# PowerSupply.net
KiCad netlist of a schematic drawn in Altium Designer
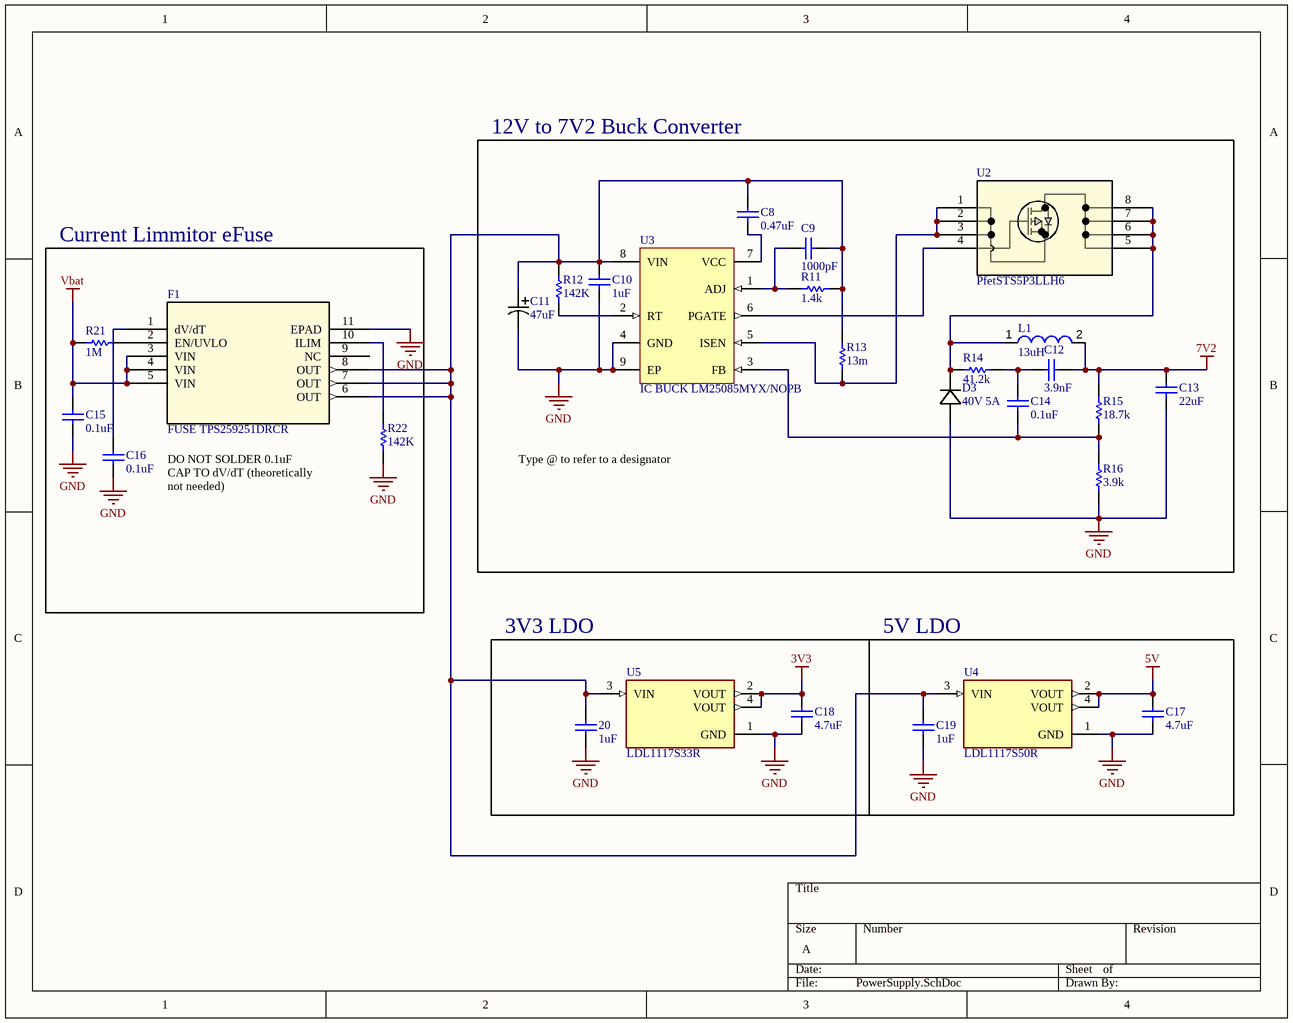
[diagram p0: PowerSupply.SchDoc]

(export (version "E")
  (design (tool "Eeschema 10.0.6"))
  (components
    (comp (ref "20")
      (value "1uF")
      (footprint "RES 0805")
      (fields
        (field (name "MANUFACTURER") "Samsung")
        (field (name "MANUFACTURER PART NUMBER") "CL21B105KBFNNNE")
      )
      (libsource (lib "Schlib1") (part "CAP CER 1uF 10% 50V 0805"))
    )
    (comp (ref "C8")
      (value "0.47uF")
      (footprint "RES 0805")
      (fields
        (field (name "MANUFACTURER") "Murata")
        (field (name "MANUFACTURER PART NUMBER") "GRM21BR71H474KA88L")
      )
      (libsource (lib "Schlib1") (part "CAP CER 0.47uF 10% 50V 0805"))
    )
    (comp (ref "C9")
      (value "1000pF")
      (footprint "RES 0805")
      (fields
        (field (name "MANUFACTURER") "KEMET")
        (field (name "MANUFACTURER PART NUMBER") "C0805C102K5RACTU")
      )
      (libsource (lib "Schlib1") (part "CAP CER 1000pF 10% 50V 0805"))
    )
    (comp (ref "C10")
      (value "1uF")
      (footprint "RES 0805")
      (fields
        (field (name "MANUFACTURER") "Samsung")
        (field (name "MANUFACTURER PART NUMBER") "CL21B105KBFNNNE")
      )
      (libsource (lib "Schlib1") (part "CAP CER 1uF 10% 50V 0805"))
    )
    (comp (ref "C11")
      (value "47uF")
      (footprint "CAP ELC 47uF")
      (fields
        (field (name "MANUFACTURER") "Nichicon")
        (field (name "MANUFACTURER PART NUMBER") "UWT1H470MCL1GS")
      )
      (libsource (lib "Schlib1") (part "CAP ELCALUM 47uF 20% 50V"))
    )
    (comp (ref "C12")
      (value "3.9nF")
      (footprint "RES 0805")
      (fields
        (field (name "MANUFACTURER") "Yageo")
        (field (name "MANUFACTURER PART NUMBER") "CC0805KRX7R9BB392")
      )
      (libsource (lib "Schlib1") (part "CAP CER 3.9nF 10% 50V 0805"))
    )
    (comp (ref "C13")
      (value "22uF")
      (footprint "RES 0805")
      (fields
        (field (name "MANUFACTURER") "Samsung")
        (field (name "MANUFACTURER PART NUMBER") "CL21A226MAYNNNE")
      )
      (libsource (lib "Schlib1") (part "CAP CER 22uF 20% 25V 0805"))
    )
    (comp (ref "C14")
      (value "0.1uF")
      (footprint "RES 0805")
      (fields
        (field (name "MANUFACTURER") "Yageo")
        (field (name "MANUFACTURER PART NUMBER") "CC0805KRX7R9BB104")
      )
      (libsource (lib "Schlib1") (part "CAP CER 0.1uF 10% 50V 0805"))
    )
    (comp (ref "C15")
      (value "0.1uF")
      (footprint "RES 0805")
      (fields
        (field (name "MANUFACTURER") "Yageo")
        (field (name "MANUFACTURER PART NUMBER") "CC0805KRX7R9BB104")
      )
      (libsource (lib "Schlib1") (part "CAP CER 0.1uF 10% 50V 0805"))
    )
    (comp (ref "C16")
      (value "0.1uF")
      (footprint "RES 0805")
      (fields
        (field (name "MANUFACTURER") "Yageo")
        (field (name "MANUFACTURER PART NUMBER") "CC0805KRX7R9BB104")
      )
      (libsource (lib "Schlib1") (part "CAP CER 0.1uF 10% 50V 0805"))
    )
    (comp (ref "C17")
      (value "4.7uF")
      (footprint "RES 0805")
      (fields
        (field (name "MANUFACTURER") "Samsung")
        (field (name "MANUFACTURER PART NUMBER") "CL21A475KAQNNNE")
      )
      (libsource (lib "Schlib1") (part "CAP CER 4.7uF 10% 25V 0805"))
    )
    (comp (ref "C18")
      (value "4.7uF")
      (footprint "RES 0805")
      (fields
        (field (name "MANUFACTURER") "Samsung")
        (field (name "MANUFACTURER PART NUMBER") "CL21A475KAQNNNE")
      )
      (libsource (lib "Schlib1") (part "CAP CER 4.7uF 10% 25V 0805"))
    )
    (comp (ref "C19")
      (value "1uF")
      (footprint "RES 0805")
      (fields
        (field (name "MANUFACTURER") "Samsung")
        (field (name "MANUFACTURER PART NUMBER") "CL21B105KBFNNNE")
      )
      (libsource (lib "Schlib1") (part "CAP CER 1uF 10% 50V 0805"))
    )
    (comp (ref "D3")
      (value "40V 5A")
      (footprint "DIODE SCHOTTKY 40V 5A")
      (description "Rectifier Diode, Schottky, 1 Phase, 1 Element, 5A, 40V V(RRM), Silicon, DO-214AC")
      (fields (field (name "MANUFACTURER") "MCC") (field (name "MANUFACTURER PART NUMBER") "SK54A-LTP"))
      (libsource (lib "Schlib1") (part "DIODE SCHOTTKY 40V 5A"))
    )
    (comp (ref "F1")
      (value "FUSE TPS259251DRCR")
      (footprint "DRC10_1P65X2P40_TEX")
      (description "Power Supply Support Circuit, Adjustable, 1 Channel, PDSO10")
      (fields
        (field (name "MANUFACTURER") "Texas Instruments")
        (field (name "MANUFACTURER PART NUMBER") "TPS259251DRCR")
      )
      (libsource (lib "Schlib1") (part "FUSE TPS259251DRCR"))
    )
    (comp (ref "L1")
      (value "13uH")
      (footprint "IND 13UH 9A 24 MOHM SMD")
      (description "General Purpose Inductor, 13uH, 20%, 1 Element, SMD, 5550")
      (fields (field (name "MANUFACTURER") "Pulse") (field (name "MANUFACTURER PART NUMBER") "PA4343.133NLT"))
      (libsource (lib "Schlib1") (part "IND 13uH 9A"))
    )
    (comp (ref "R11")
      (value "1.4k")
      (footprint "RES 0805")
      (fields
        (field (name "MANUFACTURER") "Yageo")
        (field (name "MANUFACTURER PART NUMBER") "RC0805FR-071K4L")
        (field (name "TOLERANCE") "1%")
      )
      (libsource (lib "Schlib1") (part "RES 1.4k 1% 0.125W 0805"))
    )
    (comp (ref "R12")
      (value "142K")
      (footprint "RES 0805")
      (description "Fixed Resistor, Thin Film, 0.125W, 142000ohm, 150V, 0.1% +/-Tol, 25ppm/Cel, Surface Mount, 0805")
      (fields
        (field (name "MANUFACTURER") "Yageo")
        (field (name "MANUFACTURER PART NUMBER") "RT0805BRD07142KL")
      )
      (libsource (lib "Schlib1") (part "RES 142K 0.1% 1/8W 0805"))
    )
    (comp (ref "R13")
      (value "13m")
      (footprint "RES 0805")
      (description "Resistor Thick Film 0.013Ohm 0.5% 0.5W 2-Pin 0805 T/R")
      (fields
        (field (name "MANUFACTURER") "Panasonic")
        (field (name "MANUFACTURER PART NUMBER") "ERJ-6CWDR013V")
      )
      (libsource (lib "Schlib1") (part "RES 13m 0.5% 0.5W 0805"))
    )
    (comp (ref "R14")
      (value "41.2k")
      (footprint "RES 0805")
      (fields
        (field (name "MANUFACTURER") "Vishay")
        (field (name "MANUFACTURER PART NUMBER") "CRCW080541K2FKEA")
        (field (name "TOLERANCE") "1%")
      )
      (libsource (lib "Schlib1") (part "RES 41.2K 1% 0.125W 0805"))
    )
    (comp (ref "R15")
      (value "18.7k")
      (footprint "RES 0805")
      (fields
        (field (name "MANUFACTURER") "Stackpole Electronics")
        (field (name "MANUFACTURER PART NUMBER") "RMCF0805FT18K7")
        (field (name "TOLERANCE") "1%")
      )
      (libsource (lib "Schlib1") (part "RES 18.7k 1% 0.125W 0805"))
    )
    (comp (ref "R16")
      (value "3.9k")
      (footprint "RES 0805")
      (fields
        (field (name "MANUFACTURER") "Stackpole Electronics")
        (field (name "MANUFACTURER PART NUMBER") "RMCF0805FT3K92")
        (field (name "TOLERANCE") "1%")
      )
      (libsource (lib "Schlib1") (part "RES 3.9k 1% 0.125W 0805"))
    )
    (comp (ref "R21")
      (value "1M")
      (footprint "RES 0805")
      (description "Fixed Resistor, Thin Film, 0.125W, 1000000ohm, 150V, 0.1% +/-Tol, 10ppm/Cel, Surface Mount, 0805")
      (fields
        (field (name "MANUFACTURER") "Vishay Dale")
        (field (name "MANUFACTURER PART NUMBER") "TNPW08051M00BYEA")
      )
      (libsource (lib "Schlib1") (part "RES 1M 0.1% 0.26W 0805"))
    )
    (comp (ref "R22")
      (value "142K")
      (footprint "RES 0805")
      (description "Fixed Resistor, Thin Film, 0.125W, 142000ohm, 150V, 0.1% +/-Tol, 25ppm/Cel, Surface Mount, 0805")
      (fields
        (field (name "MANUFACTURER") "Yageo")
        (field (name "MANUFACTURER PART NUMBER") "RT0805BRD07142KL")
      )
      (libsource (lib "Schlib1") (part "RES 142K 0.1% 1/8W 0805"))
    )
    (comp (ref "U2")
      (value "PfetSTS5P3LLH6")
      (footprint "STS5P3LLH6")
      (description "Power Field-Effect Transistor, 5A I(D), 1-Element, P-Channel, Metal-oxide Semiconductor FET")
      (fields
        (field (name "MANUFACTURER") "STMicroelectronics")
        (field (name "MANUFACTURER PART NUMBER") "STS5P3LLH6")
      )
      (libsource (lib "Schlib1") (part "PfetSTS5P3LLH6"))
    )
    (comp (ref "U3")
      (value "IC BUCK LM25085MYX/NOPB")
      (description "Switching Controller, Voltage-mode, 10A, 1000kHz Switching Freq-Max, PDSO8")
      (fields
        (field (name "MANUFACTURER") "TI National Semiconductor")
        (field (name "MANUFACTURER PART NUMBER") "LM25085MYX/NOPB")
      )
      (libsource (lib "Schlib1") (part "IC BUCK LM25085MYX/NOPB"))
    )
    (comp (ref "U4")
      (value "LDL1117S50R")
      (footprint "SOT230P700X180-4N")
      (description "Fixed Positive LDO Regulator, 5V, 0.6V Dropout, PDSO4")
      (fields (field (name "MANUFACTURER") "STMicroelectronics"))
      (libsource (lib "Schlib1") (part "LDL1117S50R"))
    )
    (comp (ref "U5")
      (value "LDL1117S33R")
      (footprint "SOT230P700X180-4N")
      (description "Fixed Positive LDO Regulator, 3.3V, 0.6V Dropout, PDSO4")
      (fields (field (name "MANUFACTURER") "STMicroelectronics"))
      (libsource (lib "Schlib1") (part "LDL1117S33R"))
    )
  )
  (nets
    (net (code "1") (name "3V3") (class "Default")
      (node (ref "C18") (pin "2") (pinfunction "2_2") (pintype "passive"))
      (node (ref "U5") (pin "2") (pinfunction "VOUT_2") (pintype "output"))
      (node (ref "U5") (pin "4") (pinfunction "VOUT_4") (pintype "output"))
    )
    (net (code "2") (name "5V") (class "Default")
      (node (ref "C17") (pin "2") (pinfunction "2_2") (pintype "passive"))
      (node (ref "U4") (pin "2") (pinfunction "VOUT_2") (pintype "output"))
      (node (ref "U4") (pin "4") (pinfunction "VOUT_4") (pintype "output"))
    )
    (net (code "3") (name "7V2") (class "Default")
      (node (ref "C12") (pin "2") (pinfunction "2_2") (pintype "passive"))
      (node (ref "C13") (pin "2") (pinfunction "2_2") (pintype "passive"))
      (node (ref "L1") (pin "2") (pinfunction "2_2") (pintype "passive"))
      (node (ref "R15") (pin "2") (pinfunction "2_2") (pintype "passive"))
    )
    (net (code "4") (name "GND") (class "Default")
      (node (ref "20") (pin "1") (pinfunction "1_1") (pintype "passive"))
      (node (ref "C10") (pin "1") (pinfunction "1_1") (pintype "passive"))
      (node (ref "C11") (pin "2") (pinfunction "2_2") (pintype "passive"))
      (node (ref "C13") (pin "1") (pinfunction "1_1") (pintype "passive"))
      (node (ref "C15") (pin "1") (pinfunction "1_1") (pintype "passive"))
      (node (ref "C16") (pin "1") (pinfunction "1_1") (pintype "passive"))
      (node (ref "C17") (pin "1") (pinfunction "1_1") (pintype "passive"))
      (node (ref "C18") (pin "1") (pinfunction "1_1") (pintype "passive"))
      (node (ref "C19") (pin "1") (pinfunction "1_1") (pintype "passive"))
      (node (ref "D3") (pin "2") (pinfunction "ANODE_2") (pintype "passive"))
      (node (ref "F1") (pin "11") (pinfunction "EPAD_11") (pintype "passive"))
      (node (ref "R16") (pin "1") (pinfunction "1_1") (pintype "passive"))
      (node (ref "R22") (pin "1") (pinfunction "1_1") (pintype "passive"))
      (node (ref "U3") (pin "4") (pinfunction "GND_4") (pintype "power_in"))
      (node (ref "U3") (pin "9") (pinfunction "EP_9") (pintype "power_in"))
      (node (ref "U4") (pin "1") (pinfunction "GND_1") (pintype "power_in"))
      (node (ref "U5") (pin "1") (pinfunction "GND_1") (pintype "power_in"))
    )
    (net (code "5") (name "Net-(C12-Pad1)") (class "Default")
      (node (ref "C12") (pin "1") (pinfunction "1_1") (pintype "passive"))
      (node (ref "C14") (pin "2") (pinfunction "2_2") (pintype "passive"))
      (node (ref "R14") (pin "2") (pinfunction "2_2") (pintype "passive"))
    )
    (net (code "6") (name "Net-(D3-CATHODE)") (class "Default")
      (node (ref "D3") (pin "1") (pinfunction "CATHODE_1") (pintype "passive"))
      (node (ref "L1") (pin "1") (pinfunction "1_1") (pintype "passive"))
      (node (ref "R14") (pin "1") (pinfunction "1_1") (pintype "passive"))
      (node (ref "U2") (pin "5") (pinfunction "D_5") (pintype "passive"))
      (node (ref "U2") (pin "6") (pinfunction "D_6") (pintype "passive"))
      (node (ref "U2") (pin "7") (pinfunction "D_7") (pintype "passive"))
      (node (ref "U2") (pin "8") (pinfunction "D_8") (pintype "passive"))
    )
    (net (code "7") (name "Net-(F1-EN{slash}UVLO)") (class "Default")
      (node (ref "F1") (pin "2") (pinfunction "EN/UVLO_2") (pintype "passive"))
      (node (ref "R21") (pin "1") (pinfunction "1_1") (pintype "passive"))
    )
    (net (code "8") (name "Net-(F1-ILIM)") (class "Default")
      (node (ref "F1") (pin "10") (pinfunction "ILIM_10") (pintype "passive"))
      (node (ref "R22") (pin "2") (pinfunction "2_2") (pintype "passive"))
    )
    (net (code "9") (name "Net-(F1-dV{slash}dT)") (class "Default")
      (node (ref "C16") (pin "2") (pinfunction "2_2") (pintype "passive"))
      (node (ref "F1") (pin "1") (pinfunction "dV/dT_1") (pintype "passive"))
    )
    (net (code "10") (name "Net-(U2-G)") (class "Default")
      (node (ref "U2") (pin "4") (pinfunction "G_4") (pintype "passive"))
      (node (ref "U3") (pin "6") (pinfunction "PGATE_6") (pintype "output"))
    )
    (net (code "11") (name "Net-(U3-ADJ)") (class "Default")
      (node (ref "C9") (pin "1") (pinfunction "1_1") (pintype "passive"))
      (node (ref "R11") (pin "1") (pinfunction "1_1") (pintype "passive"))
      (node (ref "U3") (pin "1") (pinfunction "ADJ_1") (pintype "input"))
    )
    (net (code "12") (name "Net-(U3-FB)") (class "Default")
      (node (ref "C14") (pin "1") (pinfunction "1_1") (pintype "passive"))
      (node (ref "R15") (pin "1") (pinfunction "1_1") (pintype "passive"))
      (node (ref "R16") (pin "2") (pinfunction "2_2") (pintype "passive"))
      (node (ref "U3") (pin "3") (pinfunction "FB_3") (pintype "input"))
    )
    (net (code "13") (name "Net-(U3-ISEN)") (class "Default")
      (node (ref "R13") (pin "1") (pinfunction "1_1") (pintype "passive"))
      (node (ref "U2") (pin "1") (pinfunction "S_1") (pintype "passive"))
      (node (ref "U2") (pin "2") (pinfunction "S_2") (pintype "passive"))
      (node (ref "U2") (pin "3") (pinfunction "S_3") (pintype "passive"))
      (node (ref "U3") (pin "5") (pinfunction "ISEN_5") (pintype "input"))
    )
    (net (code "14") (name "Net-(U3-RT)") (class "Default")
      (node (ref "R12") (pin "1") (pinfunction "1_1") (pintype "passive"))
      (node (ref "U3") (pin "2") (pinfunction "RT_2") (pintype "input"))
    )
    (net (code "15") (name "Net-(U3-VCC)") (class "Default")
      (node (ref "C8") (pin "1") (pinfunction "1_1") (pintype "passive"))
      (node (ref "U3") (pin "7") (pinfunction "VCC_7") (pintype "power_in"))
    )
    (net (code "16") (name "Net-(U3-VIN)") (class "Default")
      (node (ref "20") (pin "2") (pinfunction "2_2") (pintype "passive"))
      (node (ref "C10") (pin "2") (pinfunction "2_2") (pintype "passive"))
      (node (ref "C11") (pin "1") (pinfunction "1_1") (pintype "passive"))
      (node (ref "C19") (pin "2") (pinfunction "2_2") (pintype "passive"))
      (node (ref "C8") (pin "2") (pinfunction "2_2") (pintype "passive"))
      (node (ref "C9") (pin "2") (pinfunction "2_2") (pintype "passive"))
      (node (ref "F1") (pin "6") (pinfunction "OUT_6") (pintype "output"))
      (node (ref "F1") (pin "7") (pinfunction "OUT_7") (pintype "output"))
      (node (ref "F1") (pin "8") (pinfunction "OUT_8") (pintype "output"))
      (node (ref "R11") (pin "2") (pinfunction "2_2") (pintype "passive"))
      (node (ref "R12") (pin "2") (pinfunction "2_2") (pintype "passive"))
      (node (ref "R13") (pin "2") (pinfunction "2_2") (pintype "passive"))
      (node (ref "U3") (pin "8") (pinfunction "VIN_8") (pintype "power_in"))
      (node (ref "U4") (pin "3") (pinfunction "VIN_3") (pintype "input"))
      (node (ref "U5") (pin "3") (pinfunction "VIN_3") (pintype "input"))
    )
    (net (code "17") (name "Vbat") (class "Default")
      (node (ref "C15") (pin "2") (pinfunction "2_2") (pintype "passive"))
      (node (ref "F1") (pin "3") (pinfunction "VIN_3") (pintype "passive"))
      (node (ref "F1") (pin "4") (pinfunction "VIN_4") (pintype "passive"))
      (node (ref "F1") (pin "5") (pinfunction "VIN_5") (pintype "passive"))
      (node (ref "R21") (pin "2") (pinfunction "2_2") (pintype "passive"))
    )
    (net (code "18") (name "unconnected-(F1-NC-Pad9)") (class "Default")
      (node (ref "F1") (pin "9") (pinfunction "NC_9") (pintype "passive"))
    )
  )
)
